# z80.net
KiCad netlist of a schematic drawn in EAGLE
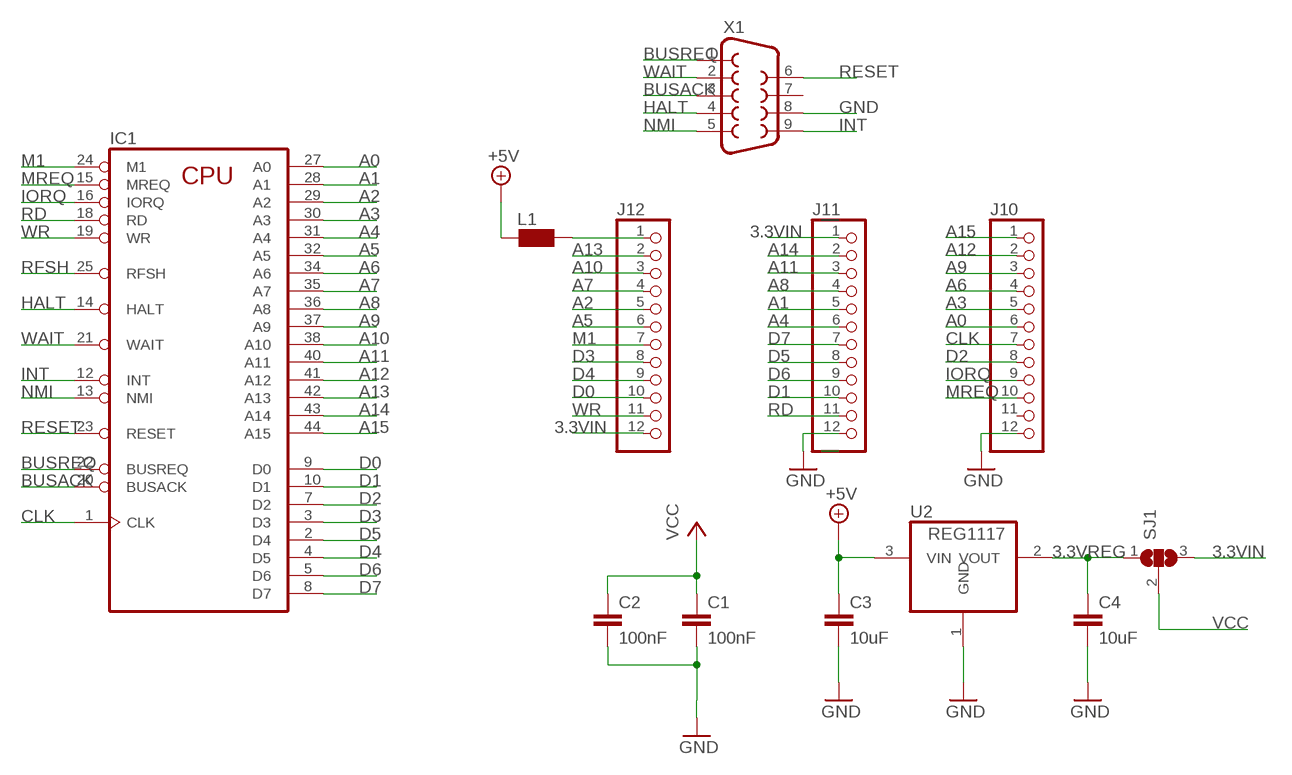
[diagram p0: schematic, sheet 1]

(export (version "E")
  (design (tool "Eeschema 10.0.6"))
  (components
    (comp (ref "C1")
      (value "100nF")
      (footprint "eagle-import:C0805K")
      (libsource (lib "eagle-import") (part "C-EUC0805K"))
    )
    (comp (ref "C2")
      (value "100nF")
      (footprint "eagle-import:C0805K")
      (libsource (lib "eagle-import") (part "C-EUC0805K"))
    )
    (comp (ref "C3")
      (value "10uF")
      (footprint "eagle-import:C0805K")
      (libsource (lib "eagle-import") (part "C-EUC0805K"))
    )
    (comp (ref "C4")
      (value "10uF")
      (footprint "eagle-import:C0805K")
      (libsource (lib "eagle-import") (part "C-EUC0805K"))
    )
    (comp (ref "IC1")
      (value "Z80CPU-F")
      (footprint "eagle-import:QFP-44")
      (libsource (lib "eagle-import") (part "Z80CPU-F"))
    )
    (comp (ref "J10")
      (value "PINHD-1X12")
      (footprint "eagle-import:1X12")
      (libsource (lib "eagle-import") (part "PINHD-1X12"))
    )
    (comp (ref "J11")
      (value "PINHD-1X12")
      (footprint "eagle-import:1X12")
      (libsource (lib "eagle-import") (part "PINHD-1X12"))
    )
    (comp (ref "J12")
      (value "PINHD-1X12")
      (footprint "eagle-import:1X12")
      (libsource (lib "eagle-import") (part "PINHD-1X12"))
    )
    (comp (ref "L1")
      (value "WE-CBF_0805")
      (footprint "eagle-import:0805")
      (libsource (lib "eagle-import") (part "WE-CBF_0805"))
    )
    (comp (ref "SJ1")
      (value "SJ2W")
      (footprint "eagle-import:SJ_2")
      (libsource (lib "eagle-import") (part "SJ2W"))
    )
    (comp (ref "U2")
      (value "REG1117")
      (footprint "eagle-import:SOT223")
      (libsource (lib "eagle-import") (part "REG1117"))
    )
    (comp (ref "X1")
      (value "F09D")
      (footprint "eagle-import:F09D")
      (libsource (lib "eagle-import") (part "F09D"))
    )
  )
  (nets
    (net (code "1") (name "+5V") (class "Default")
      (node (ref "C3") (pin "1") (pinfunction "1_1") (pintype "passive"))
      (node (ref "L1") (pin "2") (pinfunction "2_2") (pintype "passive"))
      (node (ref "U2") (pin "3") (pinfunction "VIN_3") (pintype "input"))
    )
    (net (code "2") (name "/3.3VIN") (class "Default")
      (node (ref "J11") (pin "1") (pinfunction "1_1") (pintype "passive"))
      (node (ref "J12") (pin "12") (pinfunction "12_12") (pintype "passive"))
      (node (ref "SJ1") (pin "3") (pinfunction "3_3") (pintype "passive"))
    )
    (net (code "3") (name "/3.3VREG") (class "Default")
      (node (ref "C4") (pin "1") (pinfunction "1_1") (pintype "passive"))
      (node (ref "SJ1") (pin "1") (pinfunction "1_1") (pintype "passive"))
      (node (ref "U2") (pin "2") (pinfunction "VOUT_2") (pintype "output"))
    )
    (net (code "4") (name "/A0") (class "Default")
      (node (ref "IC1") (pin "27") (pinfunction "A0_27") (pintype "output"))
      (node (ref "J10") (pin "6") (pinfunction "6_6") (pintype "passive"))
    )
    (net (code "5") (name "/A1") (class "Default")
      (node (ref "IC1") (pin "28") (pinfunction "A1_28") (pintype "output"))
      (node (ref "J11") (pin "5") (pinfunction "5_5") (pintype "passive"))
    )
    (net (code "6") (name "/A2") (class "Default")
      (node (ref "IC1") (pin "29") (pinfunction "A2_29") (pintype "output"))
      (node (ref "J12") (pin "5") (pinfunction "5_5") (pintype "passive"))
    )
    (net (code "7") (name "/A3") (class "Default")
      (node (ref "IC1") (pin "30") (pinfunction "A3_30") (pintype "output"))
      (node (ref "J10") (pin "5") (pinfunction "5_5") (pintype "passive"))
    )
    (net (code "8") (name "/A4") (class "Default")
      (node (ref "IC1") (pin "31") (pinfunction "A4_31") (pintype "output"))
      (node (ref "J11") (pin "6") (pinfunction "6_6") (pintype "passive"))
    )
    (net (code "9") (name "/A5") (class "Default")
      (node (ref "IC1") (pin "32") (pinfunction "A5_32") (pintype "output"))
      (node (ref "J12") (pin "6") (pinfunction "6_6") (pintype "passive"))
    )
    (net (code "10") (name "/A6") (class "Default")
      (node (ref "IC1") (pin "34") (pinfunction "A6_34") (pintype "output"))
      (node (ref "J10") (pin "4") (pinfunction "4_4") (pintype "passive"))
    )
    (net (code "11") (name "/A7") (class "Default")
      (node (ref "IC1") (pin "35") (pinfunction "A7_35") (pintype "output"))
      (node (ref "J12") (pin "4") (pinfunction "4_4") (pintype "passive"))
    )
    (net (code "12") (name "/A8") (class "Default")
      (node (ref "IC1") (pin "36") (pinfunction "A8_36") (pintype "output"))
      (node (ref "J11") (pin "4") (pinfunction "4_4") (pintype "passive"))
    )
    (net (code "13") (name "/A9") (class "Default")
      (node (ref "IC1") (pin "37") (pinfunction "A9_37") (pintype "output"))
      (node (ref "J10") (pin "3") (pinfunction "3_3") (pintype "passive"))
    )
    (net (code "14") (name "/A10") (class "Default")
      (node (ref "IC1") (pin "38") (pinfunction "A10_38") (pintype "output"))
      (node (ref "J12") (pin "3") (pinfunction "3_3") (pintype "passive"))
    )
    (net (code "15") (name "/A11") (class "Default")
      (node (ref "IC1") (pin "40") (pinfunction "A11_40") (pintype "output"))
      (node (ref "J11") (pin "3") (pinfunction "3_3") (pintype "passive"))
    )
    (net (code "16") (name "/A12") (class "Default")
      (node (ref "IC1") (pin "41") (pinfunction "A12_41") (pintype "output"))
      (node (ref "J10") (pin "2") (pinfunction "2_2") (pintype "passive"))
    )
    (net (code "17") (name "/A13") (class "Default")
      (node (ref "IC1") (pin "42") (pinfunction "A13_42") (pintype "output"))
      (node (ref "J12") (pin "2") (pinfunction "2_2") (pintype "passive"))
    )
    (net (code "18") (name "/A14") (class "Default")
      (node (ref "IC1") (pin "43") (pinfunction "A14_43") (pintype "output"))
      (node (ref "J11") (pin "2") (pinfunction "2_2") (pintype "passive"))
    )
    (net (code "19") (name "/A15") (class "Default")
      (node (ref "IC1") (pin "44") (pinfunction "A15_44") (pintype "output"))
      (node (ref "J10") (pin "1") (pinfunction "1_1") (pintype "passive"))
    )
    (net (code "20") (name "/BUSACK") (class "Default")
      (node (ref "IC1") (pin "20") (pinfunction "BUSACK_20") (pintype "output"))
      (node (ref "X1") (pin "3") (pinfunction "3_3") (pintype "passive"))
    )
    (net (code "21") (name "/BUSREQ") (class "Default")
      (node (ref "IC1") (pin "22") (pinfunction "BUSREQ_22") (pintype "input"))
      (node (ref "X1") (pin "1") (pinfunction "1_1") (pintype "passive"))
    )
    (net (code "22") (name "/CLK") (class "Default")
      (node (ref "IC1") (pin "1") (pinfunction "CLK_1") (pintype "input"))
      (node (ref "J10") (pin "7") (pinfunction "7_7") (pintype "passive"))
    )
    (net (code "23") (name "/D0") (class "Default")
      (node (ref "IC1") (pin "9") (pinfunction "D0_9") (pintype "bidirectional"))
      (node (ref "J12") (pin "10") (pinfunction "10_10") (pintype "passive"))
    )
    (net (code "24") (name "/D1") (class "Default")
      (node (ref "IC1") (pin "10") (pinfunction "D1_10") (pintype "bidirectional"))
      (node (ref "J11") (pin "10") (pinfunction "10_10") (pintype "passive"))
    )
    (net (code "25") (name "/D2") (class "Default")
      (node (ref "IC1") (pin "7") (pinfunction "D2_7") (pintype "bidirectional"))
      (node (ref "J10") (pin "8") (pinfunction "8_8") (pintype "passive"))
    )
    (net (code "26") (name "/D3") (class "Default")
      (node (ref "IC1") (pin "3") (pinfunction "D3_3") (pintype "bidirectional"))
      (node (ref "J12") (pin "8") (pinfunction "8_8") (pintype "passive"))
    )
    (net (code "27") (name "/D4") (class "Default")
      (node (ref "IC1") (pin "4") (pinfunction "D5_4") (pintype "bidirectional"))
      (node (ref "J12") (pin "9") (pinfunction "9_9") (pintype "passive"))
    )
    (net (code "28") (name "/D5") (class "Default")
      (node (ref "IC1") (pin "2") (pinfunction "D4_2") (pintype "bidirectional"))
      (node (ref "J11") (pin "8") (pinfunction "8_8") (pintype "passive"))
    )
    (net (code "29") (name "/D6") (class "Default")
      (node (ref "IC1") (pin "5") (pinfunction "D6_5") (pintype "bidirectional"))
      (node (ref "J11") (pin "9") (pinfunction "9_9") (pintype "passive"))
    )
    (net (code "30") (name "/D7") (class "Default")
      (node (ref "IC1") (pin "8") (pinfunction "D7_8") (pintype "bidirectional"))
      (node (ref "J11") (pin "7") (pinfunction "7_7") (pintype "passive"))
    )
    (net (code "31") (name "/HALT") (class "Default")
      (node (ref "IC1") (pin "14") (pinfunction "HALT_14") (pintype "output"))
      (node (ref "X1") (pin "4") (pinfunction "4_4") (pintype "passive"))
    )
    (net (code "32") (name "/INT") (class "Default")
      (node (ref "IC1") (pin "12") (pinfunction "INT_12") (pintype "input"))
      (node (ref "X1") (pin "9") (pinfunction "9_9") (pintype "passive"))
    )
    (net (code "33") (name "/IORQ") (class "Default")
      (node (ref "IC1") (pin "16") (pinfunction "IORQ_16") (pintype "output"))
      (node (ref "J10") (pin "9") (pinfunction "9_9") (pintype "passive"))
    )
    (net (code "34") (name "/M1") (class "Default")
      (node (ref "IC1") (pin "24") (pinfunction "M1_24") (pintype "output"))
      (node (ref "J12") (pin "7") (pinfunction "7_7") (pintype "passive"))
    )
    (net (code "35") (name "/MREQ") (class "Default")
      (node (ref "IC1") (pin "15") (pinfunction "MREQ_15") (pintype "output"))
      (node (ref "J10") (pin "10") (pinfunction "10_10") (pintype "passive"))
    )
    (net (code "36") (name "/NMI") (class "Default")
      (node (ref "IC1") (pin "13") (pinfunction "NMI_13") (pintype "input"))
      (node (ref "X1") (pin "5") (pinfunction "5_5") (pintype "passive"))
    )
    (net (code "37") (name "/RD") (class "Default")
      (node (ref "IC1") (pin "18") (pinfunction "RD_18") (pintype "output"))
      (node (ref "J11") (pin "11") (pinfunction "11_11") (pintype "passive"))
    )
    (net (code "38") (name "/RESET") (class "Default")
      (node (ref "IC1") (pin "23") (pinfunction "RESET_23") (pintype "input"))
      (node (ref "X1") (pin "6") (pinfunction "6_6") (pintype "passive"))
    )
    (net (code "39") (name "/RFSH") (class "Default")
      (node (ref "IC1") (pin "25") (pinfunction "RFSH_25") (pintype "output"))
    )
    (net (code "40") (name "/WAIT") (class "Default")
      (node (ref "IC1") (pin "21") (pinfunction "WAIT_21") (pintype "input"))
      (node (ref "X1") (pin "2") (pinfunction "2_2") (pintype "passive"))
    )
    (net (code "41") (name "/WR") (class "Default")
      (node (ref "IC1") (pin "19") (pinfunction "WR_19") (pintype "output"))
      (node (ref "J12") (pin "11") (pinfunction "11_11") (pintype "passive"))
    )
    (net (code "42") (name "GND") (class "Default")
      (node (ref "C1") (pin "2") (pinfunction "2_2") (pintype "passive"))
      (node (ref "C2") (pin "2") (pinfunction "2_2") (pintype "passive"))
      (node (ref "C3") (pin "2") (pinfunction "2_2") (pintype "passive"))
      (node (ref "C4") (pin "2") (pinfunction "2_2") (pintype "passive"))
      (node (ref "J10") (pin "12") (pinfunction "12_12") (pintype "passive"))
      (node (ref "J11") (pin "12") (pinfunction "12_12") (pintype "passive"))
      (node (ref "U2") (pin "1") (pinfunction "GND_1") (pintype "power_in"))
      (node (ref "X1") (pin "8") (pinfunction "8_8") (pintype "passive"))
    )
    (net (code "43") (name "Net-(J12-Pad1)") (class "Default")
      (node (ref "J12") (pin "1") (pinfunction "1_1") (pintype "passive"))
      (node (ref "L1") (pin "1") (pinfunction "1_1") (pintype "passive"))
    )
    (net (code "44") (name "VCC") (class "Default")
      (node (ref "C1") (pin "1") (pinfunction "1_1") (pintype "passive"))
      (node (ref "C2") (pin "1") (pinfunction "1_1") (pintype "passive"))
      (node (ref "SJ1") (pin "2") (pinfunction "2_2") (pintype "passive"))
    )
    (net (code "45") (name "unconnected-(J10-Pad11)") (class "Default")
      (node (ref "J10") (pin "11") (pinfunction "11_11") (pintype "passive"))
    )
    (net (code "46") (name "unconnected-(X1-Pad7)") (class "Default")
      (node (ref "X1") (pin "7") (pinfunction "7_7") (pintype "passive"))
    )
  )
)
